# relay.net
KiCad netlist of a schematic drawn in Altium Designer
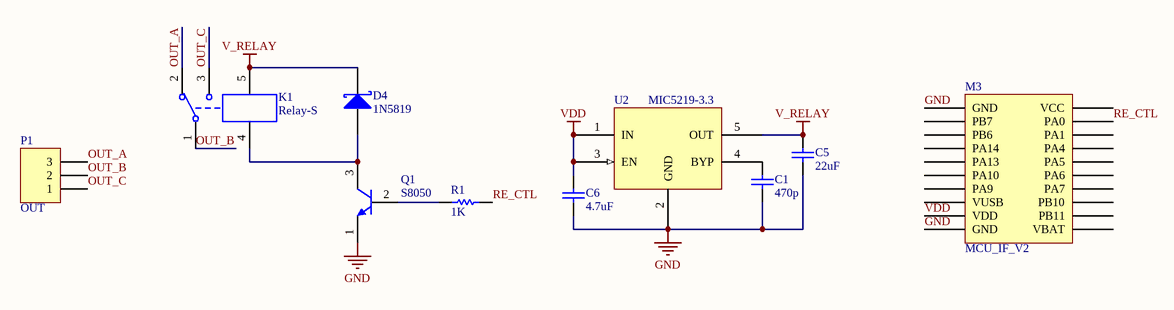
[diagram p0: relay.SchDoc]

(export (version "E")
  (design (tool "Eeschema 10.0.6"))
  (components
    (comp (ref "C1")
      (value "470p")
      (footprint "C-1608[0603]")
      (description "Capacitor (Semiconductor SIM Model)")
      (fields (field (name "Comment") "Cap Semi") (field (name "PUBLISHER") "Altium Limited"))
      (libsource (lib "Miscellaneous Devices") (part "Cap Semi"))
    )
    (comp (ref "C5")
      (value "22uF")
      (footprint "C-2012[0805]")
      (description "Capacitor (Semiconductor SIM Model)")
      (fields (field (name "Comment") "Cap Semi") (field (name "PUBLISHER") "Altium Limited"))
      (libsource (lib "Miscellaneous Devices") (part "Cap Semi"))
    )
    (comp (ref "C6")
      (value "4.7uF")
      (footprint "C-1608[0603]")
      (description "Capacitor (Semiconductor SIM Model)")
      (fields (field (name "Comment") "Cap Semi") (field (name "PUBLISHER") "Altium Limited"))
      (libsource (lib "Miscellaneous Devices") (part "Cap Semi"))
    )
    (comp (ref "D4")
      (value "1N5819")
      (footprint "PcbLib1:SOD123")
      (description "Schottky Diode")
      (fields (field (name "PUBLISHER") "Altium Limited"))
      (libsource (lib "Miscellaneous Devices") (part "D Schottky"))
    )
    (comp (ref "K1")
      (value "Relay-S")
      (footprint "Relay-JZC-32F-ZS")
      (description "Single-Pole Dual-Throw Relay")
      (fields (field (name "PUBLISHER") "Altium Limited"))
      (libsource (lib "Miscellaneous Devices") (part "Relay-SPDT"))
    )
    (comp (ref "M3")
      (value "MCU_IF_V2")
      (footprint "MCU_IF_V2")
      (libsource (lib "MCU_IF") (part "MCU_IF_V1"))
    )
    (comp (ref "P1")
      (value "OUT")
      (footprint "Edge5.08mm3P")
      (description "Header, 3-Pin")
      (fields (field (name "PUBLISHER") "Altium Limited"))
      (libsource (lib "Miscellaneous Connectors") (part "Header 3"))
    )
    (comp (ref "Q1")
      (value "S8050")
      (footprint "SOT23B")
      (description "NPN General Purpose Amplifier")
      (fields (field (name "PUBLISHER") "Altium Limited"))
      (libsource (lib "Miscellaneous Devices") (part "2N3904"))
    )
    (comp (ref "R1")
      (value "1K")
      (footprint "R-1608[0603]")
      (description "Semiconductor Resistor")
      (fields (field (name "Comment") "Res Semi") (field (name "PUBLISHER") "Altium Limited"))
      (libsource (lib "Miscellaneous Devices") (part "Res Semi"))
    )
    (comp (ref "U2")
      (value "MIC5219-3.3")
      (footprint "SOT23-5")
      (description "500mA-Peak Output LDO Regulator")
      (libsource (lib "Schlib1") (part "MIC5219"))
    )
  )
  (nets
    (net (code "1") (name "/OUT_A") (class "Default")
      (node (ref "K1") (pin "2") (pinfunction "2_2") (pintype "passive"))
      (node (ref "P1") (pin "3") (pinfunction "3_3") (pintype "passive"))
    )
    (net (code "2") (name "/OUT_B") (class "Default")
      (node (ref "K1") (pin "1") (pinfunction "1_1") (pintype "passive"))
      (node (ref "P1") (pin "2") (pinfunction "2_2") (pintype "passive"))
    )
    (net (code "3") (name "/OUT_C") (class "Default")
      (node (ref "K1") (pin "3") (pinfunction "3_3") (pintype "passive"))
      (node (ref "P1") (pin "1") (pinfunction "1_1") (pintype "passive"))
    )
    (net (code "4") (name "/RE_CTL") (class "Default")
      (node (ref "M3") (pin "19") (pinfunction "PA0_19") (pintype "passive"))
      (node (ref "R1") (pin "2") (pinfunction "2_2") (pintype "passive"))
    )
    (net (code "5") (name "GND") (class "Default")
      (node (ref "C1") (pin "2") (pinfunction "2_2") (pintype "passive"))
      (node (ref "C5") (pin "2") (pinfunction "2_2") (pintype "passive"))
      (node (ref "C6") (pin "2") (pinfunction "2_2") (pintype "passive"))
      (node (ref "M3") (pin "1") (pinfunction "GND_1") (pintype "passive"))
      (node (ref "M3") (pin "10") (pinfunction "GND_10") (pintype "passive"))
      (node (ref "Q1") (pin "1") (pinfunction "E_1") (pintype "passive"))
      (node (ref "U2") (pin "2") (pinfunction "GND_2") (pintype "passive"))
    )
    (net (code "6") (name "Net-(D4-A)") (class "Default")
      (node (ref "D4") (pin "1") (pinfunction "A_1") (pintype "passive"))
      (node (ref "K1") (pin "4") (pinfunction "4_4") (pintype "passive"))
      (node (ref "Q1") (pin "3") (pinfunction "C_3") (pintype "passive"))
    )
    (net (code "7") (name "Net-(Q1-B)") (class "Default")
      (node (ref "Q1") (pin "2") (pinfunction "B_2") (pintype "passive"))
      (node (ref "R1") (pin "1") (pinfunction "1_1") (pintype "passive"))
    )
    (net (code "8") (name "Net-(U2-BYP)") (class "Default")
      (node (ref "C1") (pin "1") (pinfunction "1_1") (pintype "passive"))
      (node (ref "U2") (pin "4") (pinfunction "BYP_4") (pintype "passive"))
    )
    (net (code "9") (name "VDD") (class "Default")
      (node (ref "C6") (pin "1") (pinfunction "1_1") (pintype "passive"))
      (node (ref "M3") (pin "9") (pinfunction "VDD_9") (pintype "passive"))
      (node (ref "U2") (pin "1") (pinfunction "IN_1") (pintype "power_in"))
      (node (ref "U2") (pin "3") (pinfunction "EN_3") (pintype "input"))
    )
    (net (code "10") (name "V_RELAY") (class "Default")
      (node (ref "C5") (pin "1") (pinfunction "1_1") (pintype "passive"))
      (node (ref "D4") (pin "2") (pinfunction "K_2") (pintype "passive"))
      (node (ref "K1") (pin "5") (pinfunction "5_5") (pintype "passive"))
      (node (ref "U2") (pin "5") (pinfunction "OUT_5") (pintype "passive"))
    )
    (net (code "11") (name "unconnected-(M3-PA1-Pad18)") (class "Default")
      (node (ref "M3") (pin "18") (pinfunction "PA1_18") (pintype "passive"))
    )
    (net (code "12") (name "unconnected-(M3-PA4-Pad17)") (class "Default")
      (node (ref "M3") (pin "17") (pinfunction "PA4_17") (pintype "passive"))
    )
    (net (code "13") (name "unconnected-(M3-PA5-Pad16)") (class "Default")
      (node (ref "M3") (pin "16") (pinfunction "PA5_16") (pintype "passive"))
    )
    (net (code "14") (name "unconnected-(M3-PA6-Pad15)") (class "Default")
      (node (ref "M3") (pin "15") (pinfunction "PA6_15") (pintype "passive"))
    )
    (net (code "15") (name "unconnected-(M3-PA7-Pad14)") (class "Default")
      (node (ref "M3") (pin "14") (pinfunction "PA7_14") (pintype "passive"))
    )
    (net (code "16") (name "unconnected-(M3-PA9-Pad7)") (class "Default")
      (node (ref "M3") (pin "7") (pinfunction "PA9_7") (pintype "passive"))
    )
    (net (code "17") (name "unconnected-(M3-PA10-Pad6)") (class "Default")
      (node (ref "M3") (pin "6") (pinfunction "PA10_6") (pintype "passive"))
    )
    (net (code "18") (name "unconnected-(M3-PA13-Pad5)") (class "Default")
      (node (ref "M3") (pin "5") (pinfunction "PA13_5") (pintype "passive"))
    )
    (net (code "19") (name "unconnected-(M3-PA14-Pad4)") (class "Default")
      (node (ref "M3") (pin "4") (pinfunction "PA14_4") (pintype "passive"))
    )
    (net (code "20") (name "unconnected-(M3-PB6-Pad3)") (class "Default")
      (node (ref "M3") (pin "3") (pinfunction "PB6_3") (pintype "passive"))
    )
    (net (code "21") (name "unconnected-(M3-PB7-Pad2)") (class "Default")
      (node (ref "M3") (pin "2") (pinfunction "PB7_2") (pintype "passive"))
    )
    (net (code "22") (name "unconnected-(M3-PB10-Pad13)") (class "Default")
      (node (ref "M3") (pin "13") (pinfunction "PB10_13") (pintype "passive"))
    )
    (net (code "23") (name "unconnected-(M3-PB11-Pad12)") (class "Default")
      (node (ref "M3") (pin "12") (pinfunction "PB11_12") (pintype "passive"))
    )
    (net (code "24") (name "unconnected-(M3-VBAT-Pad11)") (class "Default")
      (node (ref "M3") (pin "11") (pinfunction "VBAT_11") (pintype "passive"))
    )
    (net (code "25") (name "unconnected-(M3-VCC-Pad20)") (class "Default")
      (node (ref "M3") (pin "20") (pinfunction "VCC_20") (pintype "passive"))
    )
    (net (code "26") (name "unconnected-(M3-VUSB-Pad8)") (class "Default")
      (node (ref "M3") (pin "8") (pinfunction "VUSB_8") (pintype "passive"))
    )
  )
)
